# ProPrj_UCC21520__2026-01-25.net
KiCad netlist of a schematic drawn in EasyEDA Pro
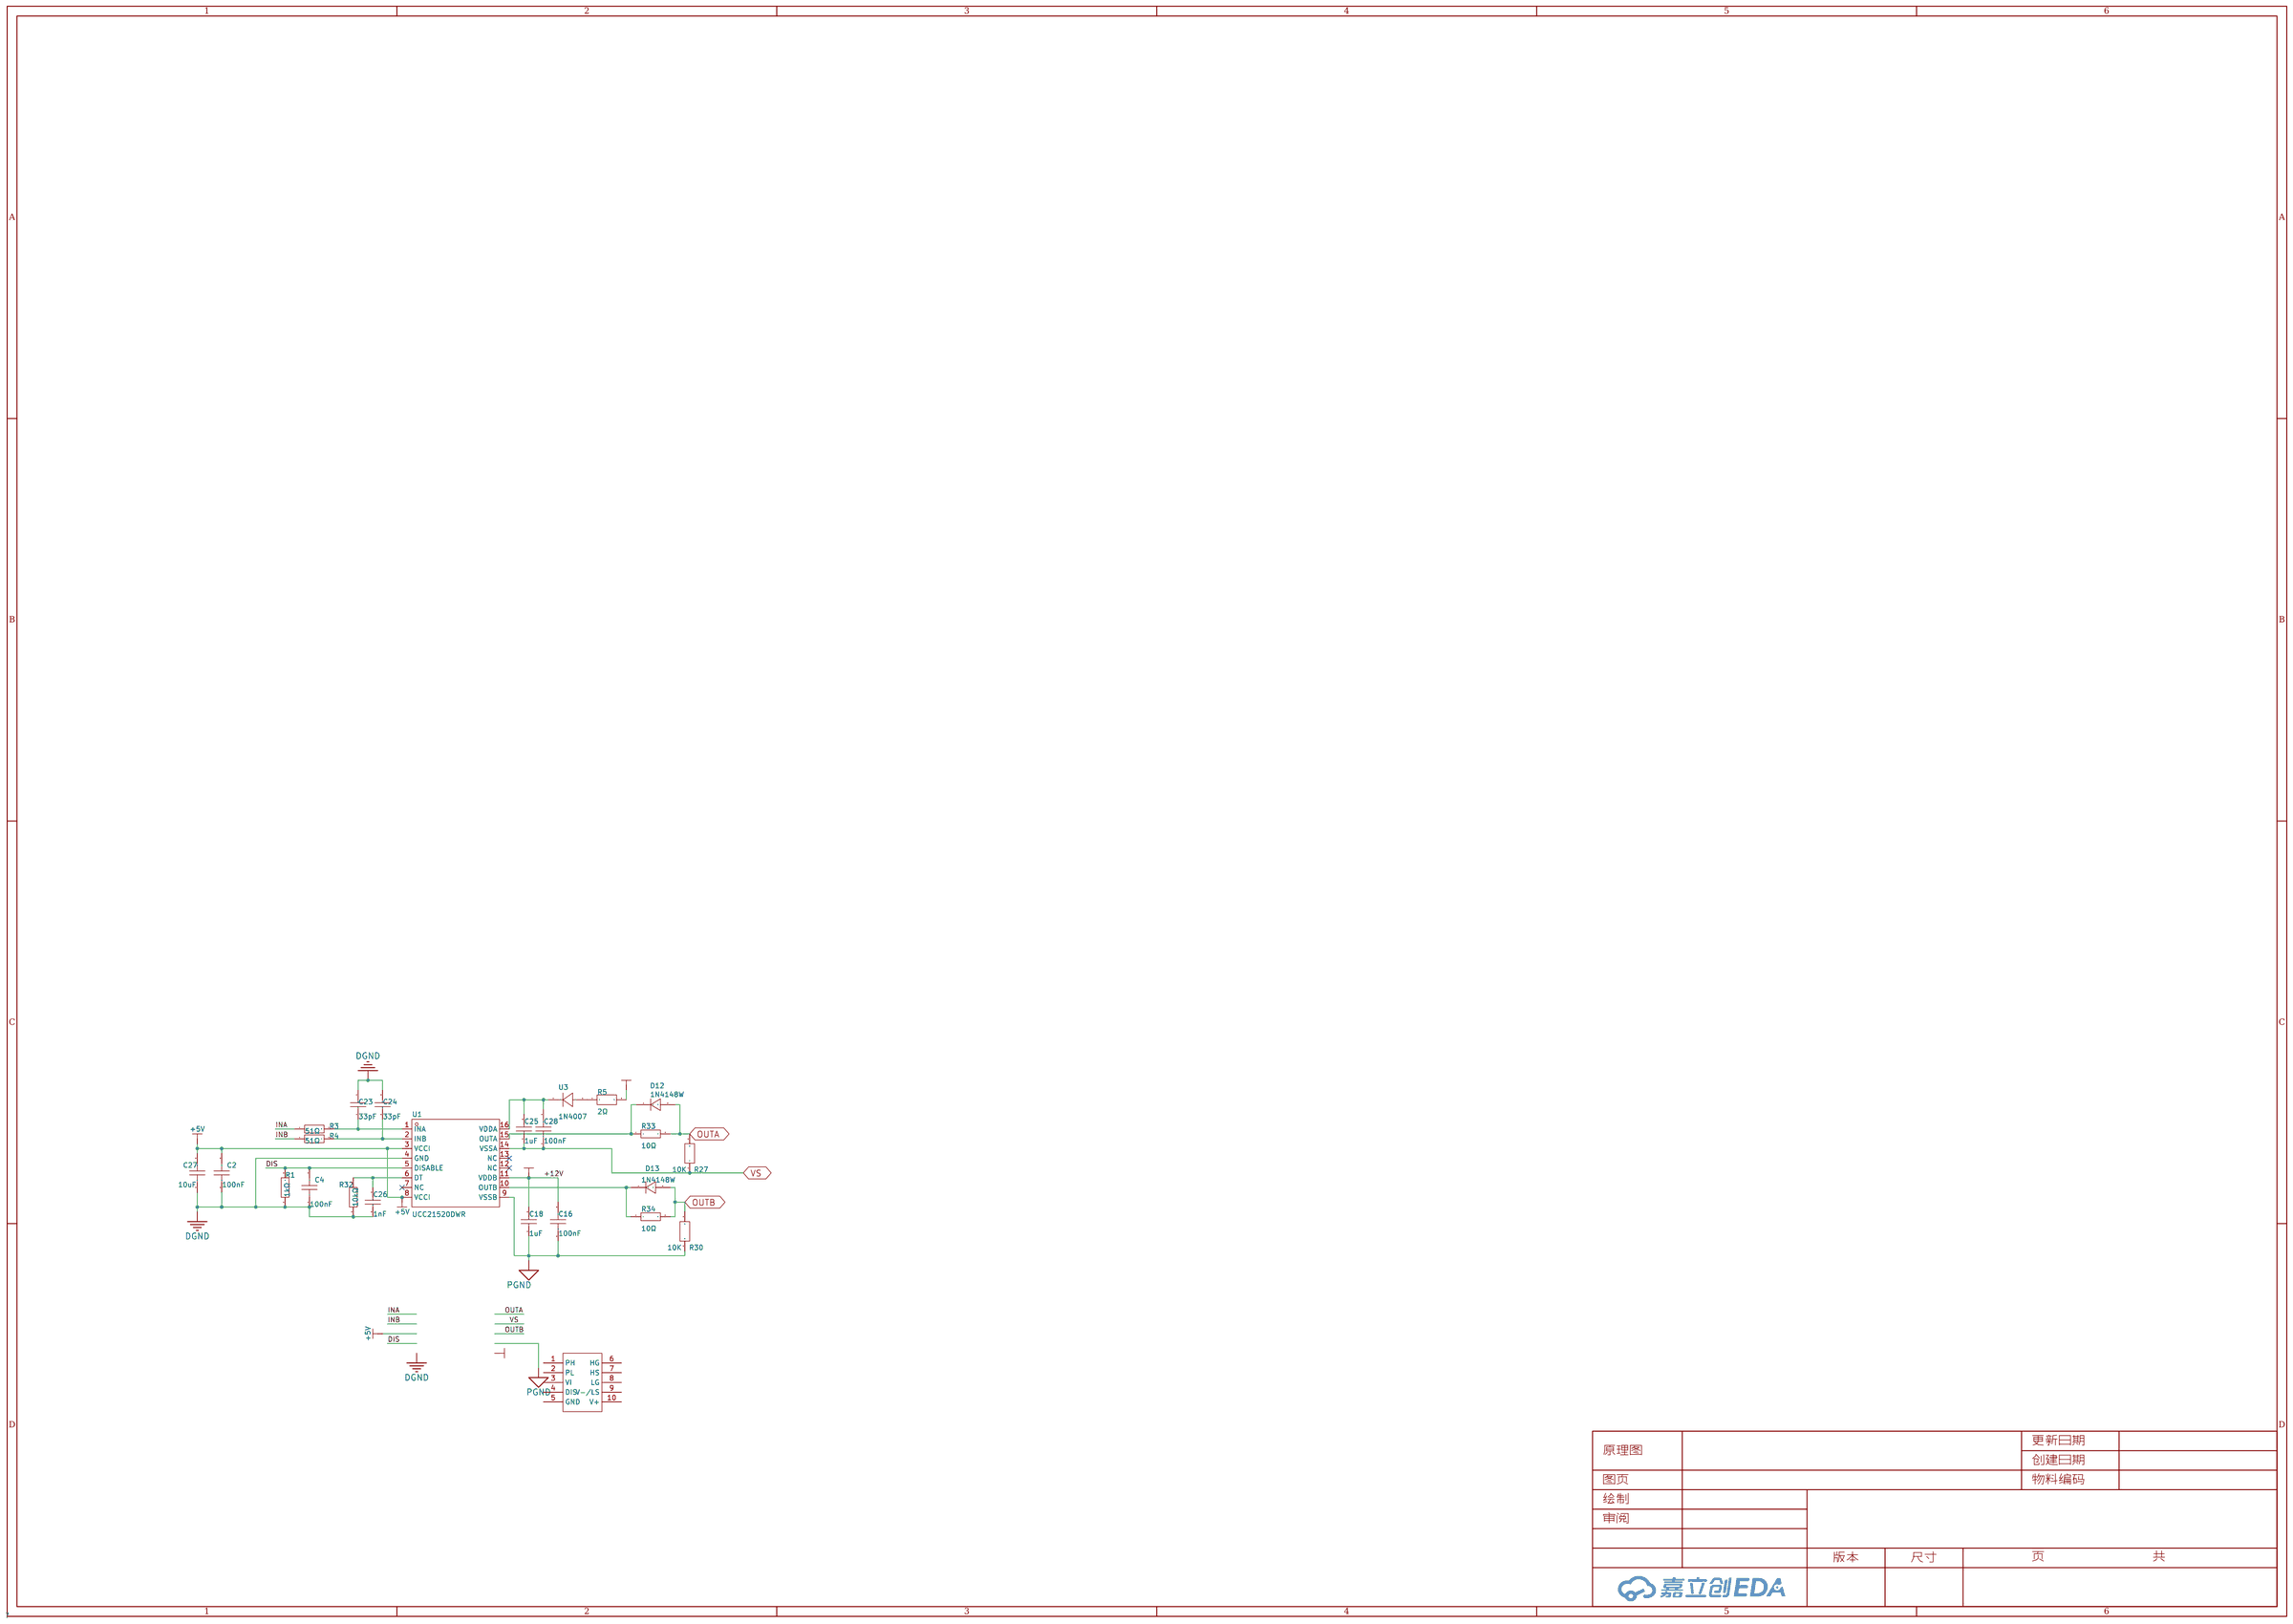
[diagram p0: schematic sheet]

(export (version "E")
  (design (tool "Eeschema 10.0.6"))
  (components
    (comp (ref "C2")
      (value "100nF")
      (footprint "easyedapro:C0603")
      (fields
        (field (name "Manufacturer Part") "CC0603KRX7R9BB104")
        (field (name "Manufacturer") "YAGEO(国巨)")
      )
      (libsource (lib "easyedapro") (part "CapAcitance"))
    )
    (comp (ref "C4")
      (value "100nF")
      (footprint "easyedapro:C0603")
      (fields
        (field (name "Manufacturer Part") "CC0603KRX7R9BB104")
        (field (name "Manufacturer") "YAGEO(国巨)")
      )
      (libsource (lib "easyedapro") (part "CapAcitance"))
    )
    (comp (ref "C16")
      (value "100nF")
      (footprint "easyedapro:C0603")
      (description "容值:100nF;精度:±10%;额定电压:50V;材质(温度系数):X7R;")
      (fields
        (field (name "Manufacturer Part") "CC0603KRX7R9BB104")
        (field (name "Manufacturer") "YAGEO(国巨)")
      )
      (libsource (lib "easyedapro") (part "CC0603KRX7R9BB104"))
    )
    (comp (ref "C18")
      (value "1uF")
      (footprint "easyedapro:C0603")
      (description "容值:1uF;精度:±10%;额定电压:50V;材质(温度系数):X5R;")
      (fields
        (field (name "Manufacturer Part") "CL10A105KB8NNNC")
        (field (name "Manufacturer") "SAMSUNG(三星)")
      )
      (libsource (lib "easyedapro") (part "CL10A105KB8NNNC"))
    )
    (comp (ref "C23")
      (value "33pF")
      (footprint "easyedapro:C0603")
      (description "容值:33pF;精度:±5%;额定电压:50V;材质(温度系数):C0G;")
      (fields
        (field (name "Manufacturer Part") "CL10C330JB8NNNC")
        (field (name "Manufacturer") "SAMSUNG(三星)")
      )
      (libsource (lib "easyedapro") (part "CL10C330JB8NNNC"))
    )
    (comp (ref "C24")
      (value "33pF")
      (footprint "easyedapro:C0603")
      (description "容值:33pF;精度:±5%;额定电压:50V;材质(温度系数):C0G;")
      (fields
        (field (name "Manufacturer Part") "CL10C330JB8NNNC")
        (field (name "Manufacturer") "SAMSUNG(三星)")
      )
      (libsource (lib "easyedapro") (part "CL10C330JB8NNNC"))
    )
    (comp (ref "C25")
      (value "1uF")
      (footprint "easyedapro:C0603")
      (description "容值:1uF;精度:±10%;额定电压:50V;材质(温度系数):X5R;")
      (fields
        (field (name "Manufacturer Part") "CL10A105KB8NNNC")
        (field (name "Manufacturer") "SAMSUNG(三星)")
      )
      (libsource (lib "easyedapro") (part "CL10A105KB8NNNC"))
    )
    (comp (ref "C26")
      (value "1nF")
      (footprint "easyedapro:C0603")
      (description "容值:1nF;精度:±10%;额定电压:50V;材质(温度系数):X7R;")
      (fields
        (field (name "Manufacturer Part") "CL10B102KB8NNNC")
        (field (name "Manufacturer") "SAMSUNG(三星)")
      )
      (libsource (lib "easyedapro") (part "CL10B102KB8NNNC"))
    )
    (comp (ref "C27")
      (value "10uF")
      (footprint "easyedapro:C0603")
      (description "容值:10uF;精度:±10%;额定电压:10V;温度系数:X5R;")
      (fields
        (field (name "Manufacturer Part") "CGA0603X5R106K100JT")
        (field (name "Manufacturer") "HRE(芯声)")
      )
      (libsource (lib "easyedapro") (part "CGA0603X5R106K100JT"))
    )
    (comp (ref "C28")
      (value "100nF")
      (footprint "easyedapro:C0603")
      (description "容值:100nF;精度:±10%;额定电压:50V;材质(温度系数):X7R;")
      (fields
        (field (name "Manufacturer Part") "CC0603KRX7R9BB104")
        (field (name "Manufacturer") "YAGEO(国巨)")
      )
      (libsource (lib "easyedapro") (part "CC0603KRX7R9BB104"))
    )
    (comp (ref "D12")
      (value "1N4148W")
      (footprint "easyedapro:SOD-123FL_L2.6-W1.6-LS3.4-RD")
      (fields (field (name "Manufacturer") "Tak Cheong"))
      (libsource (lib "easyedapro") (part "1N4148W"))
    )
    (comp (ref "D13")
      (value "1N4148W")
      (footprint "easyedapro:SOD-123FL_L2.6-W1.6-LS3.4-RD")
      (fields (field (name "Manufacturer") "Tak Cheong"))
      (libsource (lib "easyedapro") (part "1N4148W"))
    )
    (comp (ref "R1")
      (value "1kΩ")
      (footprint "easyedapro:R0603")
      (fields
        (field (name "Manufacturer Part") "0603WAF1001T5E")
        (field (name "Manufacturer") "UNI-ROYAL(厚声)")
      )
      (libsource (lib "easyedapro") (part "电阻"))
    )
    (comp (ref "R3")
      (value "51Ω")
      (footprint "easyedapro:R0603")
      (description "电阻类型:厚膜电阻;阻值:51Ω;精度:±1%;功率:100mW;最大工作电压:75V;温度系数:±100ppm/°C;")
      (fields
        (field (name "Manufacturer Part") "0603WAF510JT5E")
        (field (name "Manufacturer") "UNI-ROYAL(厚声)")
      )
      (libsource (lib "easyedapro") (part "0603WAF510JT5E"))
    )
    (comp (ref "R4")
      (value "51Ω")
      (footprint "easyedapro:R0603")
      (description "电阻类型:厚膜电阻;阻值:51Ω;精度:±1%;功率:100mW;最大工作电压:75V;温度系数:±100ppm/°C;")
      (fields
        (field (name "Manufacturer Part") "0603WAF510JT5E")
        (field (name "Manufacturer") "UNI-ROYAL(厚声)")
      )
      (libsource (lib "easyedapro") (part "0603WAF510JT5E"))
    )
    (comp (ref "R5")
      (value "2Ω")
      (footprint "easyedapro:R0603")
      (description "电阻类型:厚膜电阻;阻值:2Ω;精度:±5%;功率:100mW;最大工作电压:75V;温度系数:±200ppm/°C;")
      (fields (field (name "Manufacturer Part") "FRC0603J2R0 TS") (field (name "Manufacturer") "FOJAN(富捷)"))
      (libsource (lib "easyedapro") (part "FRC0603J2R0 TS"))
    )
    (comp (ref "R27")
      (value "10K")
      (footprint "easyedapro:R0603")
      (libsource (lib "easyedapro") (part "10K"))
    )
    (comp (ref "R30")
      (value "10K")
      (footprint "easyedapro:R0603")
      (libsource (lib "easyedapro") (part "10K"))
    )
    (comp (ref "R32")
      (value "10kΩ")
      (footprint "easyedapro:R0603")
      (description "电阻类型:厚膜电阻;阻值:10kΩ;精度:±1%;功率:100mW;最大工作电压:75V;温度系数:±100ppm/°C;")
      (fields
        (field (name "Manufacturer Part") "0603WAF1002T5E")
        (field (name "Manufacturer") "UNI-ROYAL(厚声)")
      )
      (libsource (lib "easyedapro") (part "0603WAF1002T5E"))
    )
    (comp (ref "R33")
      (value "10Ω")
      (footprint "easyedapro:R0603")
      (description "电阻类型:厚膜电阻;阻值:10Ω;精度:±1%;功率:100mW;最大工作电压:75V;温度系数:±400ppm/°C;")
      (fields
        (field (name "Manufacturer Part") "0603WAF100JT5E")
        (field (name "Manufacturer") "UNI-ROYAL(厚声)")
      )
      (libsource (lib "easyedapro") (part "0603WAF100JT5E"))
    )
    (comp (ref "R34")
      (value "10Ω")
      (footprint "easyedapro:R0603")
      (description "电阻类型:厚膜电阻;阻值:10Ω;精度:±1%;功率:100mW;最大工作电压:75V;温度系数:±400ppm/°C;")
      (fields
        (field (name "Manufacturer Part") "0603WAF100JT5E")
        (field (name "Manufacturer") "UNI-ROYAL(厚声)")
      )
      (libsource (lib "easyedapro") (part "0603WAF100JT5E"))
    )
    (comp (ref "U1")
      (value "UCC21520DWR")
      (footprint "easyedapro:SOIC-16_L10.3-W7.5-P1.27-LS10.3-BL")
      (description "UCC21520 4A/6A、5.7 kVrms 双通道隔离式栅极驱动器")
      (fields (field (name "Manufacturer") "TI(德州仪器)"))
      (libsource (lib "easyedapro") (part "UCC21520DWR"))
    )
    (comp (ref "U2")
      (value "~")
      (footprint "easyedapro:UCC21520模块")
      (libsource (lib "easyedapro") (part "UCC21520驱动模块"))
    )
    (comp (ref "U3")
      (value "1N4007")
      (footprint "easyedapro:SMA_L4.3-W2.6-LS5.1-RD")
      (libsource (lib "easyedapro") (part "1N4007_C9900004759"))
    )
  )
  (nets
    (net (code "1") (name "+5V") (class "Default")
      (node (ref "C2") (pin "2") (pinfunction "2_2") (pintype "input"))
      (node (ref "C27") (pin "2") (pinfunction "2_2") (pintype "unspecified"))
      (node (ref "U1") (pin "3") (pinfunction "VCCI_3") (pintype "input"))
      (node (ref "U1") (pin "8") (pinfunction "VCCI_8") (pintype "input"))
    )
    (net (code "2") (name "+12V") (class "Default")
      (node (ref "C16") (pin "2") (pinfunction "2_2") (pintype "unspecified"))
      (node (ref "C18") (pin "2") (pinfunction "2_2") (pintype "input"))
      (node (ref "R5") (pin "2") (pinfunction "2_2") (pintype "unspecified"))
      (node (ref "U1") (pin "11") (pinfunction "VDDB_11") (pintype "input"))
    )
    (net (code "3") (name "/DIS") (class "Default")
      (node (ref "C4") (pin "2") (pinfunction "2_2") (pintype "input"))
      (node (ref "R1") (pin "2") (pinfunction "2_2") (pintype "input"))
      (node (ref "U1") (pin "5") (pinfunction "DISABLE_5") (pintype "input"))
    )
    (net (code "4") (name "/INA") (class "Default")
      (node (ref "R3") (pin "1") (pinfunction "1_1") (pintype "input"))
    )
    (net (code "5") (name "/INB") (class "Default")
      (node (ref "R4") (pin "1") (pinfunction "1_1") (pintype "input"))
    )
    (net (code "6") (name "DGND") (class "Default")
      (node (ref "C2") (pin "1") (pinfunction "1_1") (pintype "input"))
      (node (ref "C23") (pin "2") (pinfunction "2_2") (pintype "input"))
      (node (ref "C24") (pin "2") (pinfunction "2_2") (pintype "input"))
      (node (ref "C26") (pin "1") (pinfunction "1_1") (pintype "input"))
      (node (ref "C27") (pin "1") (pinfunction "1_1") (pintype "unspecified"))
      (node (ref "C4") (pin "1") (pinfunction "1_1") (pintype "input"))
      (node (ref "R1") (pin "1") (pinfunction "1_1") (pintype "input"))
      (node (ref "R32") (pin "1") (pinfunction "1_1") (pintype "input"))
      (node (ref "U1") (pin "4") (pinfunction "GND_4") (pintype "input"))
    )
    (net (code "7") (name "Net-(U1-DT)") (class "Default")
      (node (ref "C26") (pin "2") (pinfunction "2_2") (pintype "input"))
      (node (ref "R32") (pin "2") (pinfunction "2_2") (pintype "input"))
      (node (ref "U1") (pin "6") (pinfunction "DT_6") (pintype "input"))
    )
    (net (code "8") (name "Net-(U1-INA)") (class "Default")
      (node (ref "C23") (pin "1") (pinfunction "1_1") (pintype "input"))
      (node (ref "R3") (pin "2") (pinfunction "2_2") (pintype "input"))
      (node (ref "U1") (pin "1") (pinfunction "INA_1") (pintype "input"))
    )
    (net (code "9") (name "Net-(U1-INB)") (class "Default")
      (node (ref "C24") (pin "1") (pinfunction "1_1") (pintype "input"))
      (node (ref "R4") (pin "2") (pinfunction "2_2") (pintype "input"))
      (node (ref "U1") (pin "2") (pinfunction "INB_2") (pintype "input"))
    )
    (net (code "10") (name "Net-(U1-OUTA)") (class "Default")
      (node (ref "D12") (pin "1") (pinfunction "1_1") (pintype "unspecified"))
      (node (ref "R33") (pin "1") (pinfunction "1_1") (pintype "input"))
      (node (ref "U1") (pin "15") (pinfunction "OUTA_15") (pintype "input"))
    )
    (net (code "11") (name "Net-(U1-OUTB)") (class "Default")
      (node (ref "D13") (pin "1") (pinfunction "1_1") (pintype "unspecified"))
      (node (ref "R34") (pin "1") (pinfunction "1_1") (pintype "input"))
      (node (ref "U1") (pin "10") (pinfunction "OUTB_10") (pintype "input"))
    )
    (net (code "12") (name "Net-(U1-VDDA)") (class "Default")
      (node (ref "C25") (pin "2") (pinfunction "2_2") (pintype "input"))
      (node (ref "C28") (pin "2") (pinfunction "2_2") (pintype "unspecified"))
      (node (ref "U1") (pin "16") (pinfunction "VDDA_16") (pintype "input"))
      (node (ref "U3") (pin "1") (pinfunction "K_1") (pintype "unspecified"))
    )
    (net (code "13") (name "Net-(U3-A)") (class "Default")
      (node (ref "R5") (pin "1") (pinfunction "1_1") (pintype "unspecified"))
      (node (ref "U3") (pin "2") (pinfunction "A_2") (pintype "unspecified"))
    )
    (net (code "14") (name "OUTA") (class "Default")
      (node (ref "D12") (pin "2") (pinfunction "2_2") (pintype "unspecified"))
      (node (ref "R27") (pin "2") (pinfunction "2_2") (pintype "unspecified"))
      (node (ref "R33") (pin "2") (pinfunction "2_2") (pintype "input"))
    )
    (net (code "15") (name "OUTB") (class "Default")
      (node (ref "D13") (pin "2") (pinfunction "2_2") (pintype "unspecified"))
      (node (ref "R30") (pin "2") (pinfunction "2_2") (pintype "unspecified"))
      (node (ref "R34") (pin "2") (pinfunction "2_2") (pintype "input"))
    )
    (net (code "16") (name "PGND") (class "Default")
      (node (ref "C16") (pin "1") (pinfunction "1_1") (pintype "unspecified"))
      (node (ref "C18") (pin "1") (pinfunction "1_1") (pintype "input"))
      (node (ref "R30") (pin "1") (pinfunction "1_1") (pintype "unspecified"))
      (node (ref "U1") (pin "9") (pinfunction "VSSB_9") (pintype "input"))
    )
    (net (code "17") (name "VS") (class "Default")
      (node (ref "C25") (pin "1") (pinfunction "1_1") (pintype "input"))
      (node (ref "C28") (pin "1") (pinfunction "1_1") (pintype "unspecified"))
      (node (ref "R27") (pin "1") (pinfunction "1_1") (pintype "unspecified"))
      (node (ref "U1") (pin "14") (pinfunction "VSSA_14") (pintype "input"))
    )
    (net (code "18") (name "unconnected-(U1-NC-Pad7)") (class "Default")
      (node (ref "U1") (pin "7") (pinfunction "NC_7") (pintype "input+no_connect"))
    )
    (net (code "19") (name "unconnected-(U1-NC-Pad12)") (class "Default")
      (node (ref "U1") (pin "12") (pinfunction "NC_12") (pintype "input+no_connect"))
    )
    (net (code "20") (name "unconnected-(U1-NC-Pad13)") (class "Default")
      (node (ref "U1") (pin "13") (pinfunction "NC_13") (pintype "input+no_connect"))
    )
    (net (code "21") (name "unconnected-(U2-DIS-Pad4)") (class "Default")
      (node (ref "U2") (pin "4") (pinfunction "DIS_4") (pintype "input"))
    )
    (net (code "22") (name "unconnected-(U2-GND-Pad5)") (class "Default")
      (node (ref "U2") (pin "5") (pinfunction "GND_5") (pintype "input"))
    )
    (net (code "23") (name "unconnected-(U2-HG-Pad6)") (class "Default")
      (node (ref "U2") (pin "6") (pinfunction "HG_6") (pintype "input"))
    )
    (net (code "24") (name "unconnected-(U2-HS-Pad7)") (class "Default")
      (node (ref "U2") (pin "7") (pinfunction "HS_7") (pintype "input"))
    )
    (net (code "25") (name "unconnected-(U2-LG-Pad8)") (class "Default")
      (node (ref "U2") (pin "8") (pinfunction "LG_8") (pintype "input"))
    )
    (net (code "26") (name "unconnected-(U2-PH-Pad1)") (class "Default")
      (node (ref "U2") (pin "1") (pinfunction "PH_1") (pintype "input"))
    )
    (net (code "27") (name "unconnected-(U2-PL-Pad2)") (class "Default")
      (node (ref "U2") (pin "2") (pinfunction "PL_2") (pintype "input"))
    )
    (net (code "28") (name "unconnected-(U2-V+-Pad10)") (class "Default")
      (node (ref "U2") (pin "10") (pinfunction "V+_10") (pintype "input"))
    )
    (net (code "29") (name "unconnected-(U2-V-{slash}LS-Pad9)") (class "Default")
      (node (ref "U2") (pin "9") (pinfunction "V-/LS_9") (pintype "input"))
    )
    (net (code "30") (name "unconnected-(U2-VI-Pad3)") (class "Default")
      (node (ref "U2") (pin "3") (pinfunction "VI_3") (pintype "input"))
    )
  )
)
